# v1_2.net
KiCad netlist of a schematic drawn in Altium Designer
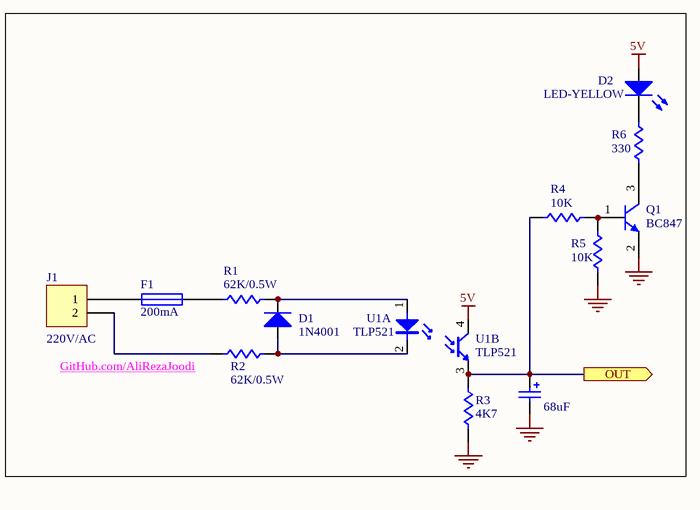
[diagram p0: v1.2.SchDoc]

(export (version "E")
  (design (tool "Eeschema 10.0.6"))
  (components
    (comp (ref "C1")
      (value "68uF")
      (footprint "Cap_D")
      (description "Polarized Capacitor (Radial)")
      (fields
        (field (name "MANUFACTURER") "Generic Components")
        (field (name "Comment") "CAP")
        (field (name "PUBLISHER") "Altium Limited")
      )
      (libsource (lib "Miscellaneous Devices") (part "Cap Pol1"))
    )
    (comp (ref "D1")
      (value "1N4001")
      (footprint "MELF-D3516-1406")
      (description "Default Diode")
      (fields (field (name "MANUFACTURER") "Generic Components") (field (name "PUBLISHER") "Altium Limited"))
      (libsource (lib "Miscellaneous Devices") (part "Diode"))
    )
    (comp (ref "D2")
      (value "LED-YELLOW")
      (footprint "0805_Diode")
      (description "Typical INFRARED GaAs LED")
      (fields (field (name "MANUFACTURER") "Generic Components") (field (name "PUBLISHER") "Altium Limited"))
      (libsource (lib "Miscellaneous Devices") (part "LED"))
    )
    (comp (ref "F1")
      (value "200mA")
      (footprint "PIN-W2/E2.8")
      (description "Fuse")
      (fields (field (name "PUBLISHER") "Altium Limited"))
      (libsource (lib "Miscellaneous Devices") (part "Fuse 1"))
    )
    (comp (ref "J1")
      (value "J9")
      (footprint "Fonics_2PIN_1")
      (description "Header, 2-Pin")
      (fields (field (name "PUBLISHER") "Altium Limited"))
      (libsource (lib "Miscellaneous Connectors") (part "Header 2"))
    )
    (comp (ref "Q1")
      (value "BC847")
      (footprint "SOT23-3N")
      (description "Silicon Bipolar Transistor")
      (libsource (lib "my Libraries") (part "BC847"))
    )
    (comp (ref "R1")
      (value "62K/0.5W")
      (footprint "0805")
      (description "Resistor")
      (fields (field (name "MANUFACTURER") "Generic Components") (field (name "PUBLISHER") "Altium Limited"))
      (libsource (lib "Miscellaneous Devices") (part "Res1"))
    )
    (comp (ref "R2")
      (value "62K/0.5W")
      (footprint "0805")
      (description "Resistor")
      (fields (field (name "MANUFACTURER") "Generic Components") (field (name "PUBLISHER") "Altium Limited"))
      (libsource (lib "Miscellaneous Devices") (part "Res1"))
    )
    (comp (ref "R3")
      (value "4K7")
      (footprint "0805")
      (description "Resistor")
      (fields (field (name "MANUFACTURER") "Generic Components") (field (name "PUBLISHER") "Altium Limited"))
      (libsource (lib "Miscellaneous Devices") (part "Res1"))
    )
    (comp (ref "R4")
      (value "10K")
      (footprint "0805")
      (description "Resistor")
      (fields (field (name "MANUFACTURER") "Generic Components") (field (name "PUBLISHER") "Altium Limited"))
      (libsource (lib "Miscellaneous Devices") (part "Res1"))
    )
    (comp (ref "R5")
      (value "10K")
      (footprint "0805")
      (description "Resistor")
      (fields (field (name "MANUFACTURER") "Generic Components") (field (name "PUBLISHER") "Altium Limited"))
      (libsource (lib "Miscellaneous Devices") (part "Res1"))
    )
    (comp (ref "R6")
      (value "330")
      (footprint "0805")
      (description "Resistor")
      (fields (field (name "MANUFACTURER") "Generic Components") (field (name "PUBLISHER") "Altium Limited"))
      (libsource (lib "Miscellaneous Devices") (part "Res1"))
    )
    (comp (ref "U1")
      (value "TLP521")
      (footprint "SMD_4PIN")
      (fields (field (name "PUBLISHER") "Altium Limited"))
      (libsource (lib "my Libraries") (part "Optoisolator"))
    )
  )
  (nets
    (net (code "1") (name "/OUT") (class "Default")
      (node (ref "C1") (pin "1") (pinfunction "1_1") (pintype "passive"))
      (node (ref "R3") (pin "1") (pinfunction "1_1") (pintype "passive"))
      (node (ref "R4") (pin "1") (pinfunction "1_1") (pintype "passive"))
      (node (ref "U1") (pin "3") (pinfunction "E_3") (pintype "passive"))
    )
    (net (code "2") (name "5V") (class "Default")
      (node (ref "D2") (pin "1") (pinfunction "A_1") (pintype "passive"))
      (node (ref "U1") (pin "4") (pinfunction "C_4") (pintype "passive"))
    )
    (net (code "3") (name "GND") (class "Default")
      (node (ref "C1") (pin "2") (pinfunction "2_2") (pintype "passive"))
      (node (ref "Q1") (pin "2") (pinfunction "E_2") (pintype "passive"))
      (node (ref "R3") (pin "2") (pinfunction "2_2") (pintype "passive"))
      (node (ref "R5") (pin "1") (pinfunction "1_1") (pintype "passive"))
    )
    (net (code "4") (name "Net-(D1-A)") (class "Default")
      (node (ref "D1") (pin "1") (pinfunction "A_1") (pintype "passive"))
      (node (ref "R2") (pin "2") (pinfunction "2_2") (pintype "passive"))
      (node (ref "U1") (pin "2") (pinfunction "K_2") (pintype "power_in"))
    )
    (net (code "5") (name "Net-(D1-K)") (class "Default")
      (node (ref "D1") (pin "2") (pinfunction "K_2") (pintype "passive"))
      (node (ref "R1") (pin "2") (pinfunction "2_2") (pintype "passive"))
      (node (ref "U1") (pin "1") (pinfunction "A_1") (pintype "power_in"))
    )
    (net (code "6") (name "Net-(D2-K)") (class "Default")
      (node (ref "D2") (pin "2") (pinfunction "K_2") (pintype "passive"))
      (node (ref "R6") (pin "1") (pinfunction "1_1") (pintype "passive"))
    )
    (net (code "7") (name "Net-(F1-Pad1)") (class "Default")
      (node (ref "F1") (pin "1") (pinfunction "1_1") (pintype "passive"))
      (node (ref "J1") (pin "1") (pinfunction "1_1") (pintype "passive"))
    )
    (net (code "8") (name "Net-(F1-Pad2)") (class "Default")
      (node (ref "F1") (pin "2") (pinfunction "2_2") (pintype "passive"))
      (node (ref "R1") (pin "1") (pinfunction "1_1") (pintype "passive"))
    )
    (net (code "9") (name "Net-(J1-Pad2)") (class "Default")
      (node (ref "J1") (pin "2") (pinfunction "2_2") (pintype "passive"))
      (node (ref "R2") (pin "1") (pinfunction "1_1") (pintype "passive"))
    )
    (net (code "10") (name "Net-(Q1-B)") (class "Default")
      (node (ref "Q1") (pin "1") (pinfunction "B_1") (pintype "passive"))
      (node (ref "R4") (pin "2") (pinfunction "2_2") (pintype "passive"))
      (node (ref "R5") (pin "2") (pinfunction "2_2") (pintype "passive"))
    )
    (net (code "11") (name "Net-(Q1-C)") (class "Default")
      (node (ref "Q1") (pin "3") (pinfunction "C_3") (pintype "passive"))
      (node (ref "R6") (pin "2") (pinfunction "2_2") (pintype "passive"))
    )
  )
)
